# 07_ux.net
KiCad netlist of a schematic drawn in Altium Designer
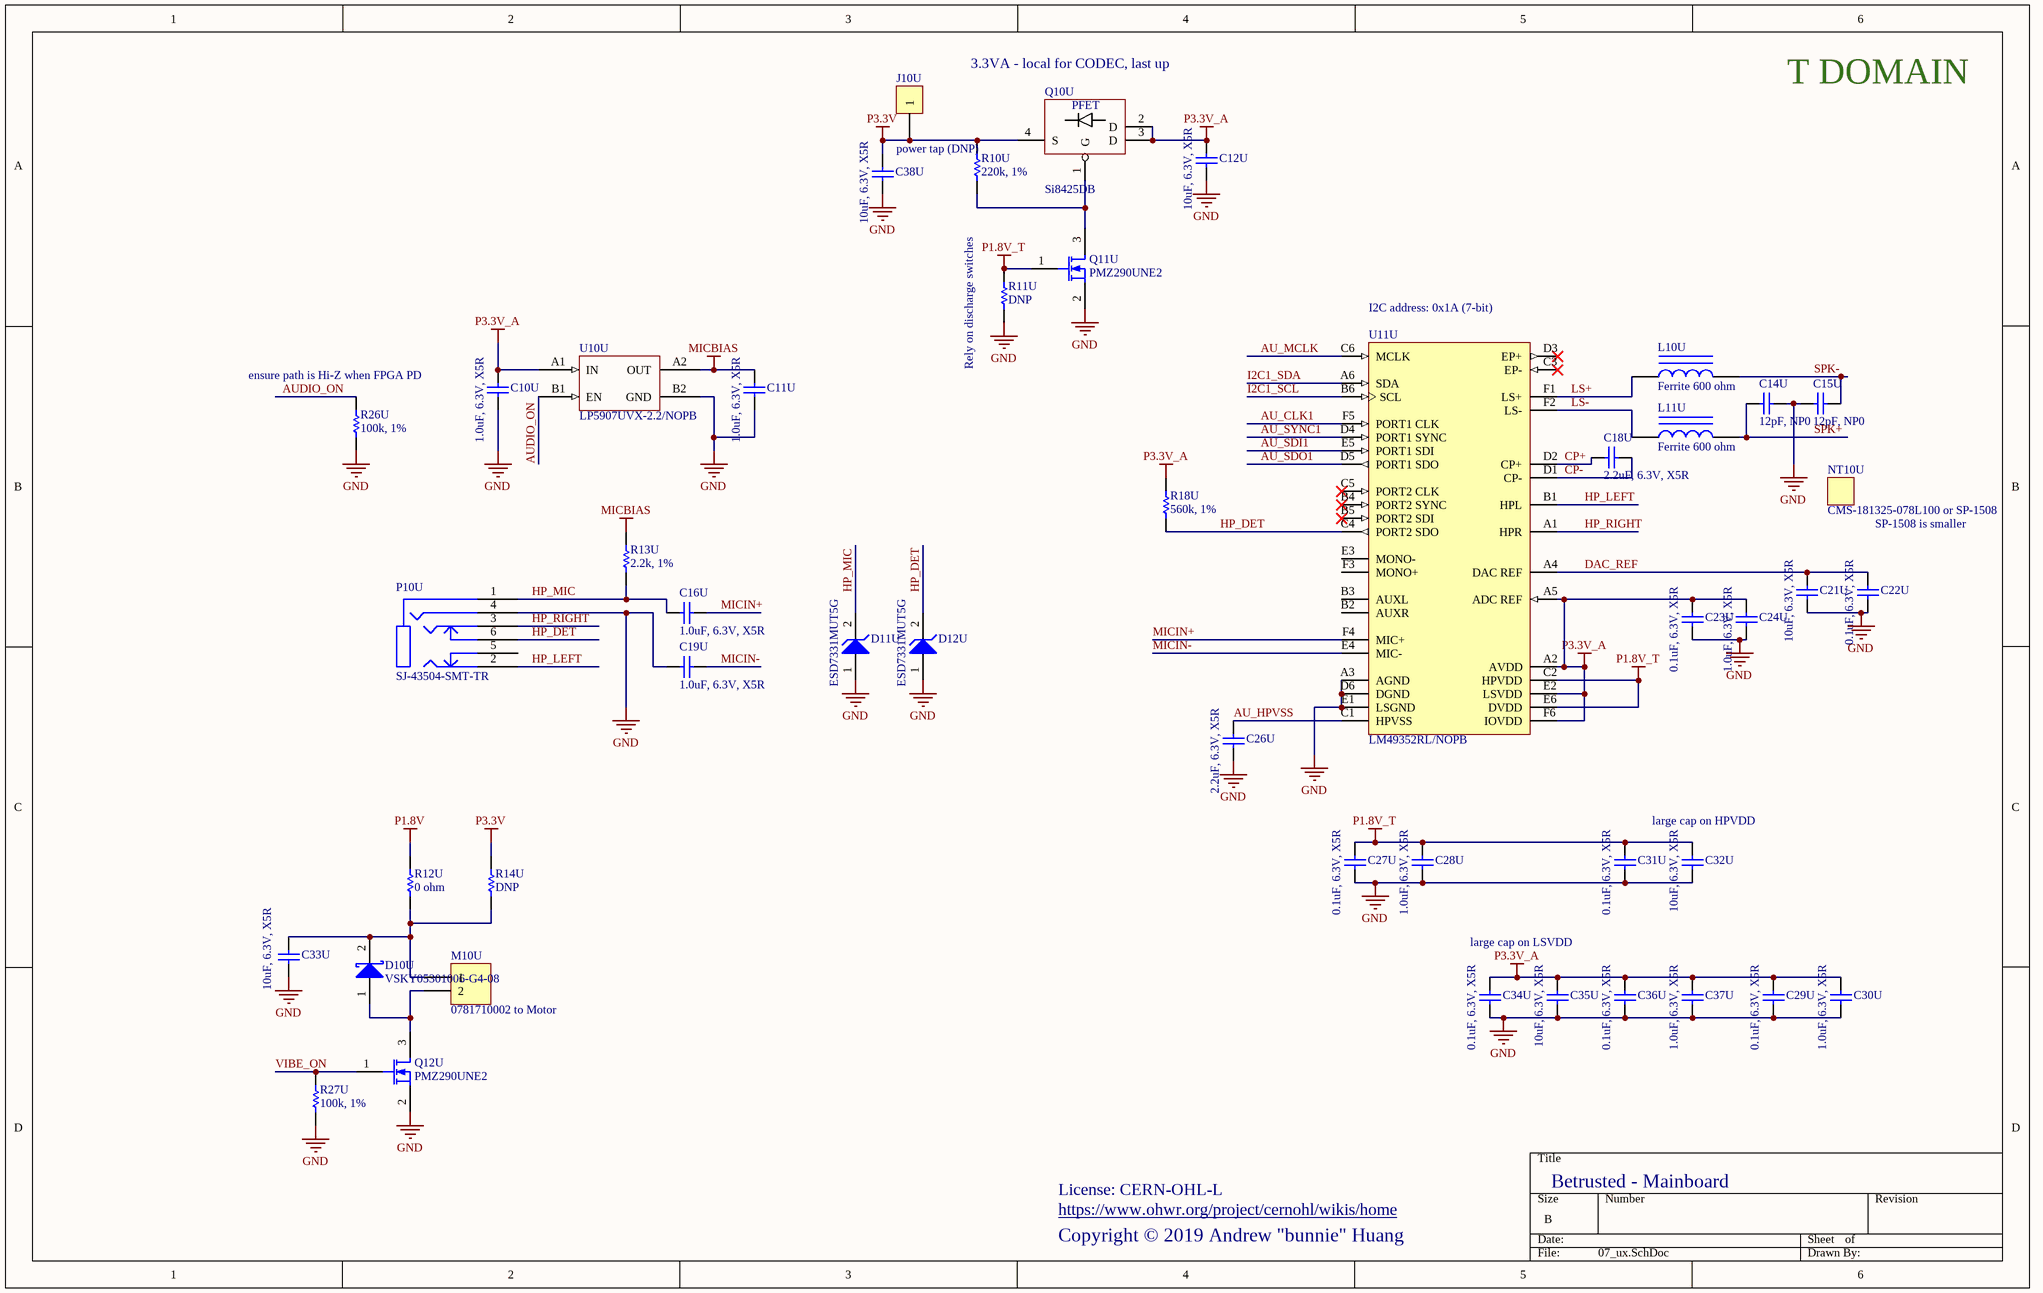
[diagram p0: 07_ux.SchDoc]

(export (version "E")
  (design (tool "Eeschema 10.0.6"))
  (components
    (comp (ref "C10U")
      (value "1.0uF, 6.3V, X5R")
      (footprint "B_CAP0201")
      (description "Capacitor (Semiconductor SIM Model)")
      (fields (field (name "MPN") "GRM033R60J105MEA2D"))
      (libsource (lib "Miscellaneous Devices") (part "Cap Semi"))
    )
    (comp (ref "C11U")
      (value "1.0uF, 6.3V, X5R")
      (footprint "B_CAP0201")
      (description "Capacitor (Semiconductor SIM Model)")
      (fields (field (name "MPN") "GRM033R60J105MEA2D"))
      (libsource (lib "Miscellaneous Devices") (part "Cap Semi"))
    )
    (comp (ref "C12U")
      (value "10uF, 6.3V, X5R")
      (footprint "B_CAP0603")
      (description "Capacitor (Semiconductor SIM Model)")
      (fields (field (name "MPN") "CL10A106MQ8NNNC"))
      (libsource (lib "Miscellaneous Devices") (part "Cap Semi"))
    )
    (comp (ref "C14U")
      (value "12pF, NP0")
      (footprint "B_CAP0201")
      (description "Capacitor (Semiconductor SIM Model)")
      (fields (field (name "MPN") "GRM0335C1E120JA01D"))
      (libsource (lib "Miscellaneous Devices") (part "Cap Semi"))
    )
    (comp (ref "C15U")
      (value "12pF, NP0")
      (footprint "B_CAP0201")
      (description "Capacitor (Semiconductor SIM Model)")
      (fields (field (name "MPN") "GRM0335C1E120JA01D"))
      (libsource (lib "Miscellaneous Devices") (part "Cap Semi"))
    )
    (comp (ref "C16U")
      (value "1.0uF, 6.3V, X5R")
      (footprint "B_CAP0201")
      (description "Capacitor (Semiconductor SIM Model)")
      (fields (field (name "MPN") "GRM033R60J105MEA2D"))
      (libsource (lib "Miscellaneous Devices") (part "Cap Semi"))
    )
    (comp (ref "C18U")
      (value "2.2uF, 6.3V, X5R")
      (footprint "B_CAP0402")
      (description "Capacitor (Semiconductor SIM Model)")
      (fields (field (name "MPN") "CL05A225MQ5NNNC"))
      (libsource (lib "Miscellaneous Devices") (part "Cap Semi"))
    )
    (comp (ref "C19U")
      (value "1.0uF, 6.3V, X5R")
      (footprint "B_CAP0201")
      (description "Capacitor (Semiconductor SIM Model)")
      (fields (field (name "MPN") "GRM033R60J105MEA2D"))
      (libsource (lib "Miscellaneous Devices") (part "Cap Semi"))
    )
    (comp (ref "C21U")
      (value "10uF, 6.3V, X5R")
      (footprint "B_CAP0603")
      (description "Capacitor (Semiconductor SIM Model)")
      (fields (field (name "MPN") "CL10A106MQ8NNNC"))
      (libsource (lib "Miscellaneous Devices") (part "Cap Semi"))
    )
    (comp (ref "C22U")
      (value "0.1uF, 6.3V, X5R")
      (footprint "B_CAP0201")
      (description "Capacitor (Semiconductor SIM Model)")
      (fields (field (name "MPN") "CL03A104KQ3NNNC"))
      (libsource (lib "Miscellaneous Devices") (part "Cap Semi"))
    )
    (comp (ref "C23U")
      (value "0.1uF, 6.3V, X5R")
      (footprint "B_CAP0201")
      (description "Capacitor (Semiconductor SIM Model)")
      (fields (field (name "MPN") "CL03A104KQ3NNNC"))
      (libsource (lib "Miscellaneous Devices") (part "Cap Semi"))
    )
    (comp (ref "C24U")
      (value "1.0uF, 6.3V, X5R")
      (footprint "B_CAP0201")
      (description "Capacitor (Semiconductor SIM Model)")
      (fields (field (name "MPN") "GRM033R60J105MEA2D"))
      (libsource (lib "Miscellaneous Devices") (part "Cap Semi"))
    )
    (comp (ref "C26U")
      (value "2.2uF, 6.3V, X5R")
      (footprint "B_CAP0402")
      (description "Capacitor (Semiconductor SIM Model)")
      (fields (field (name "MPN") "CL05A225MQ5NNNC"))
      (libsource (lib "Miscellaneous Devices") (part "Cap Semi"))
    )
    (comp (ref "C27U")
      (value "0.1uF, 6.3V, X5R")
      (footprint "B_CAP0201")
      (description "Capacitor (Semiconductor SIM Model)")
      (fields (field (name "MPN") "CL03A104KQ3NNNC"))
      (libsource (lib "Miscellaneous Devices") (part "Cap Semi"))
    )
    (comp (ref "C28U")
      (value "1.0uF, 6.3V, X5R")
      (footprint "B_CAP0201")
      (description "Capacitor (Semiconductor SIM Model)")
      (fields (field (name "MPN") "GRM033R60J105MEA2D"))
      (libsource (lib "Miscellaneous Devices") (part "Cap Semi"))
    )
    (comp (ref "C29U")
      (value "0.1uF, 6.3V, X5R")
      (footprint "B_CAP0201")
      (description "Capacitor (Semiconductor SIM Model)")
      (fields (field (name "MPN") "CL03A104KQ3NNNC"))
      (libsource (lib "Miscellaneous Devices") (part "Cap Semi"))
    )
    (comp (ref "C30U")
      (value "1.0uF, 6.3V, X5R")
      (footprint "B_CAP0201")
      (description "Capacitor (Semiconductor SIM Model)")
      (fields (field (name "MPN") "GRM033R60J105MEA2D"))
      (libsource (lib "Miscellaneous Devices") (part "Cap Semi"))
    )
    (comp (ref "C31U")
      (value "0.1uF, 6.3V, X5R")
      (footprint "B_CAP0201")
      (description "Capacitor (Semiconductor SIM Model)")
      (fields (field (name "MPN") "CL03A104KQ3NNNC"))
      (libsource (lib "Miscellaneous Devices") (part "Cap Semi"))
    )
    (comp (ref "C32U")
      (value "10uF, 6.3V, X5R")
      (footprint "B_CAP0603")
      (description "Capacitor (Semiconductor SIM Model)")
      (fields (field (name "MPN") "CL10A106MQ8NNNC"))
      (libsource (lib "Miscellaneous Devices") (part "Cap Semi"))
    )
    (comp (ref "C33U")
      (value "10uF, 6.3V, X5R")
      (footprint "B_CAP0603")
      (description "Capacitor (Semiconductor SIM Model)")
      (fields (field (name "MPN") "CL10A106MQ8NNNC"))
      (libsource (lib "Miscellaneous Devices") (part "Cap Semi"))
    )
    (comp (ref "C34U")
      (value "0.1uF, 6.3V, X5R")
      (footprint "B_CAP0201")
      (description "Capacitor (Semiconductor SIM Model)")
      (fields (field (name "MPN") "CL03A104KQ3NNNC"))
      (libsource (lib "Miscellaneous Devices") (part "Cap Semi"))
    )
    (comp (ref "C35U")
      (value "10uF, 6.3V, X5R")
      (footprint "B_CAP0603")
      (description "Capacitor (Semiconductor SIM Model)")
      (fields (field (name "MPN") "CL10A106MQ8NNNC"))
      (libsource (lib "Miscellaneous Devices") (part "Cap Semi"))
    )
    (comp (ref "C36U")
      (value "0.1uF, 6.3V, X5R")
      (footprint "B_CAP0201")
      (description "Capacitor (Semiconductor SIM Model)")
      (fields (field (name "MPN") "CL03A104KQ3NNNC"))
      (libsource (lib "Miscellaneous Devices") (part "Cap Semi"))
    )
    (comp (ref "C37U")
      (value "1.0uF, 6.3V, X5R")
      (footprint "B_CAP0201")
      (description "Capacitor (Semiconductor SIM Model)")
      (fields (field (name "MPN") "GRM033R60J105MEA2D"))
      (libsource (lib "Miscellaneous Devices") (part "Cap Semi"))
    )
    (comp (ref "C38U")
      (value "10uF, 6.3V, X5R")
      (footprint "B_CAP0603")
      (description "Capacitor (Semiconductor SIM Model)")
      (fields (field (name "MPN") "CL10A106MQ8NNNC"))
      (libsource (lib "Miscellaneous Devices") (part "Cap Semi"))
    )
    (comp (ref "D10U")
      (value "VSKY05301006-G4-08")
      (footprint "B_DIO0402")
      (description "Schottky Rectifier")
      (libsource (lib "Miscellaneous Devices") (part "Diode 11DQ03"))
    )
    (comp (ref "D11U")
      (value "ESD7331MUT5G")
      (footprint "D_X3DFN2_0201")
      (fields (field (name "PUBLISHER") "Altium Limited"))
      (libsource (lib "Miscellaneous Devices") (part "D Zener"))
    )
    (comp (ref "D12U")
      (value "ESD7331MUT5G")
      (footprint "D_X3DFN2_0201")
      (fields (field (name "PUBLISHER") "Altium Limited"))
      (libsource (lib "Miscellaneous Devices") (part "D Zener"))
    )
    (comp (ref "J10U")
      (value "power tap (DNP)")
      (footprint "RESTAP-0603")
      (description "Connector")
      (fields (field (name "MPN") "DNP"))
      (libsource (lib "*") (part "CON1"))
    )
    (comp (ref "L10U")
      (value "Ferrite 600 ohm")
      (footprint "B_IND0603")
      (description "Magnetic-Core Inductor")
      (fields (field (name "MPN") "BLM18AG601SN1D"))
      (libsource (lib "Miscellaneous Devices") (part "Inductor Iron"))
    )
    (comp (ref "L11U")
      (value "Ferrite 600 ohm")
      (footprint "B_IND0603")
      (description "Magnetic-Core Inductor")
      (fields (field (name "MPN") "BLM18AG601SN1D"))
      (libsource (lib "Miscellaneous Devices") (part "Inductor Iron"))
    )
    (comp (ref "M10U")
      (value "0781710002 to Motor")
      (footprint "MOLEX_0781710002")
      (description "Vibration motor, mid-mount 10mm")
      (fields (field (name "MPN") "0781710002") (field (name "PUBLISHER") "Altium Limited"))
      (libsource (lib "Miscellaneous Connectors") (part "Header 2"))
    )
    (comp (ref "NT10U")
      (value "CMS-181325-078L100 or SP-1508")
      (description "Placeholder for non-board BOM items")
      (libsource (lib "commonsch") (part "NOTE"))
    )
    (comp (ref "P10U")
      (value "SJ-43504-SMT-TR")
      (footprint "CUI_SJ_43504_SMT_TR_FLIP")
      (description "Mid mount audio jack")
      (libsource (lib "commonsch-new") (part "CUI_3.5MM_STEREO_MIC"))
    )
    (comp (ref "Q10U")
      (value "Si8425DB")
      (footprint "VISHAY_MICRO_FOOT_4_BUMP")
      (description "P-channel 20V 6.2A 27mOhm @ -2.5V")
      (fields (field (name "MPN") "SI8457DB-T1-E1"))
      (libsource (lib "temp-to-merge") (part "Si8425DB"))
    )
    (comp (ref "Q11U")
      (value "PMZ290UNE2")
      (footprint "SOT883")
      (description "N-Channel MOSFET")
      (fields (field (name "PUBLISHER") "Altium Limited"))
      (libsource (lib "Miscellaneous Devices") (part "MOSFET-N"))
    )
    (comp (ref "Q12U")
      (value "PMZ290UNE2")
      (footprint "SOT883")
      (description "N-Channel MOSFET")
      (fields (field (name "PUBLISHER") "Altium Limited"))
      (libsource (lib "Miscellaneous Devices") (part "MOSFET-N"))
    )
    (comp (ref "R10U")
      (value "220k, 1%")
      (footprint "B_RES0201")
      (description "Resistor")
      (fields (field (name "MPN") "ANY"))
      (libsource (lib "Miscellaneous Devices") (part "Res1"))
    )
    (comp (ref "R11U")
      (value "DNP")
      (footprint "B_RES0201")
      (description "Resistor")
      (fields (field (name "MPN") "ANY"))
      (libsource (lib "Miscellaneous Devices") (part "Res1"))
    )
    (comp (ref "R12U")
      (value "0 ohm")
      (footprint "B_RES0201")
      (description "Resistor")
      (fields (field (name "MPN") "ANY"))
      (libsource (lib "Miscellaneous Devices") (part "Res1"))
    )
    (comp (ref "R13U")
      (value "2.2k, 1%")
      (footprint "B_RES0201")
      (description "Resistor")
      (fields (field (name "MPN") "ANY"))
      (libsource (lib "Miscellaneous Devices") (part "Res1"))
    )
    (comp (ref "R14U")
      (value "DNP")
      (footprint "B_RES0201")
      (description "Resistor")
      (fields (field (name "MPN") "ANY"))
      (libsource (lib "Miscellaneous Devices") (part "Res1"))
    )
    (comp (ref "R18U")
      (value "560k, 1%")
      (footprint "B_RES0201")
      (description "Resistor")
      (fields (field (name "MPN") "ANY"))
      (libsource (lib "Miscellaneous Devices") (part "Res1"))
    )
    (comp (ref "R26U")
      (value "100k, 1%")
      (footprint "B_RES0201")
      (description "Resistor")
      (fields (field (name "MPN") "ANY"))
      (libsource (lib "Miscellaneous Devices") (part "Res1"))
    )
    (comp (ref "R27U")
      (value "100k, 1%")
      (footprint "B_RES0201")
      (description "Resistor")
      (fields (field (name "MPN") "ANY"))
      (libsource (lib "Miscellaneous Devices") (part "Res1"))
    )
    (comp (ref "U10U")
      (value "LP5907UVX-2.2/NOPB")
      (footprint "TI_YKE004")
      (description "Ultra low-noise 250mA LDO for RF and analog in DSBGA")
      (libsource (lib "commonsch-new") (part "LP5907UVX"))
    )
    (comp (ref "U11U")
      (value "LM49352RL/NOPB")
      (footprint "YPG0036AWAW")
      (libsource (lib "Copy of AMP-AUDA-LM49352-36-bunnie") (part "AMP-AUDA-LM49352-36"))
    )
  )
  (nets
    (net (code "1") (name "/AUDIO_ON") (class "Default")
      (node (ref "R26U") (pin "2") (pinfunction "2_2") (pintype "passive"))
      (node (ref "U10U") (pin "B1") (pinfunction "EN_B1") (pintype "input"))
    )
    (net (code "2") (name "/AU_CLK1") (class "Default")
      (node (ref "U11U") (pin "F5") (pinfunction "PORT1_CLK_F5") (pintype "input"))
    )
    (net (code "3") (name "/AU_HPVSS") (class "Default")
      (node (ref "C26U") (pin "2") (pinfunction "2_2") (pintype "passive"))
      (node (ref "U11U") (pin "C1") (pinfunction "HPVSS_C1") (pintype "power_in"))
    )
    (net (code "4") (name "/AU_MCLK") (class "Default")
      (node (ref "U11U") (pin "C6") (pinfunction "MCLK_C6") (pintype "input"))
    )
    (net (code "5") (name "/AU_SDI1") (class "Default")
      (node (ref "U11U") (pin "E5") (pinfunction "PORT1_SDI_E5") (pintype "input"))
    )
    (net (code "6") (name "/AU_SDO1") (class "Default")
      (node (ref "U11U") (pin "D5") (pinfunction "PORT1_SDO_D5") (pintype "output"))
    )
    (net (code "7") (name "/AU_SYNC1") (class "Default")
      (node (ref "U11U") (pin "D4") (pinfunction "PORT1_SYNC_D4") (pintype "input"))
    )
    (net (code "8") (name "/CP+") (class "Default")
      (node (ref "C18U") (pin "2") (pinfunction "2_2") (pintype "passive"))
      (node (ref "U11U") (pin "D2") (pinfunction "CP+_D2") (pintype "passive"))
    )
    (net (code "9") (name "/CP-") (class "Default")
      (node (ref "C18U") (pin "1") (pinfunction "1_1") (pintype "passive"))
      (node (ref "U11U") (pin "D1") (pinfunction "CP-_D1") (pintype "passive"))
    )
    (net (code "10") (name "/DAC_REF") (class "Default")
      (node (ref "C21U") (pin "1") (pinfunction "1_1") (pintype "passive"))
      (node (ref "C22U") (pin "1") (pinfunction "1_1") (pintype "passive"))
      (node (ref "U11U") (pin "A4") (pinfunction "DAC_REF_A4") (pintype "power_in"))
    )
    (net (code "11") (name "/HP_DET") (class "Default")
      (node (ref "D12U") (pin "2") (pinfunction "K_2") (pintype "passive"))
      (node (ref "P10U") (pin "6") (pinfunction "RING1_SW_6") (pintype "passive"))
      (node (ref "R18U") (pin "1") (pinfunction "1_1") (pintype "passive"))
      (node (ref "U11U") (pin "C4") (pinfunction "PORT2_SDO_C4") (pintype "output"))
    )
    (net (code "12") (name "/HP_LEFT") (class "Default")
      (node (ref "P10U") (pin "2") (pinfunction "TIP_2") (pintype "passive"))
      (node (ref "U11U") (pin "B1") (pinfunction "HPL_B1") (pintype "passive"))
    )
    (net (code "13") (name "/HP_MIC") (class "Default")
      (node (ref "C16U") (pin "1") (pinfunction "1_1") (pintype "passive"))
      (node (ref "D11U") (pin "2") (pinfunction "K_2") (pintype "passive"))
      (node (ref "P10U") (pin "1") (pinfunction "SLEEVE_1") (pintype "passive"))
      (node (ref "R13U") (pin "1") (pinfunction "1_1") (pintype "passive"))
    )
    (net (code "14") (name "/HP_RIGHT") (class "Default")
      (node (ref "P10U") (pin "3") (pinfunction "RING1_3") (pintype "passive"))
      (node (ref "U11U") (pin "A1") (pinfunction "HPR_A1") (pintype "passive"))
    )
    (net (code "15") (name "/I2C1_SCL") (class "Default")
      (node (ref "U11U") (pin "B6") (pinfunction "SCL_B6") (pintype "input"))
    )
    (net (code "16") (name "/I2C1_SDA") (class "Default")
      (node (ref "U11U") (pin "A6") (pinfunction "SDA_A6") (pintype "input"))
    )
    (net (code "17") (name "/LS+") (class "Default")
      (node (ref "L10U") (pin "1") (pinfunction "1_1") (pintype "passive"))
      (node (ref "U11U") (pin "F1") (pinfunction "LS+_F1") (pintype "power_in"))
    )
    (net (code "18") (name "/LS-") (class "Default")
      (node (ref "L11U") (pin "1") (pinfunction "1_1") (pintype "passive"))
      (node (ref "U11U") (pin "F2") (pinfunction "LS-_F2") (pintype "power_in"))
    )
    (net (code "19") (name "/MICIN+") (class "Default")
      (node (ref "C16U") (pin "2") (pinfunction "2_2") (pintype "passive"))
      (node (ref "U11U") (pin "F4") (pinfunction "MIC+_F4") (pintype "passive"))
    )
    (net (code "20") (name "/MICIN-") (class "Default")
      (node (ref "C19U") (pin "2") (pinfunction "2_2") (pintype "passive"))
      (node (ref "U11U") (pin "E4") (pinfunction "MIC-_E4") (pintype "passive"))
    )
    (net (code "21") (name "/SPK+") (class "Default")
      (node (ref "C14U") (pin "1") (pinfunction "1_1") (pintype "passive"))
      (node (ref "L11U") (pin "2") (pinfunction "2_2") (pintype "passive"))
    )
    (net (code "22") (name "/SPK-") (class "Default")
      (node (ref "C15U") (pin "2") (pinfunction "2_2") (pintype "passive"))
      (node (ref "L10U") (pin "2") (pinfunction "2_2") (pintype "passive"))
    )
    (net (code "23") (name "/VIBE_ON") (class "Default")
      (node (ref "Q12U") (pin "1") (pinfunction "G_1") (pintype "passive"))
      (node (ref "R27U") (pin "2") (pinfunction "2_2") (pintype "passive"))
    )
    (net (code "24") (name "GND") (class "Default")
      (node (ref "C10U") (pin "2") (pinfunction "2_2") (pintype "passive"))
      (node (ref "C11U") (pin "2") (pinfunction "2_2") (pintype "passive"))
      (node (ref "C12U") (pin "2") (pinfunction "2_2") (pintype "passive"))
      (node (ref "C14U") (pin "2") (pinfunction "2_2") (pintype "passive"))
      (node (ref "C15U") (pin "1") (pinfunction "1_1") (pintype "passive"))
      (node (ref "C19U") (pin "1") (pinfunction "1_1") (pintype "passive"))
      (node (ref "C21U") (pin "2") (pinfunction "2_2") (pintype "passive"))
      (node (ref "C22U") (pin "2") (pinfunction "2_2") (pintype "passive"))
      (node (ref "C23U") (pin "2") (pinfunction "2_2") (pintype "passive"))
      (node (ref "C24U") (pin "1") (pinfunction "1_1") (pintype "passive"))
      (node (ref "C26U") (pin "1") (pinfunction "1_1") (pintype "passive"))
      (node (ref "C27U") (pin "2") (pinfunction "2_2") (pintype "passive"))
      (node (ref "C28U") (pin "1") (pinfunction "1_1") (pintype "passive"))
      (node (ref "C29U") (pin "2") (pinfunction "2_2") (pintype "passive"))
      (node (ref "C30U") (pin "1") (pinfunction "1_1") (pintype "passive"))
      (node (ref "C31U") (pin "2") (pinfunction "2_2") (pintype "passive"))
      (node (ref "C32U") (pin "2") (pinfunction "2_2") (pintype "passive"))
      (node (ref "C33U") (pin "1") (pinfunction "1_1") (pintype "passive"))
      (node (ref "C34U") (pin "2") (pinfunction "2_2") (pintype "passive"))
      (node (ref "C35U") (pin "2") (pinfunction "2_2") (pintype "passive"))
      (node (ref "C36U") (pin "2") (pinfunction "2_2") (pintype "passive"))
      (node (ref "C37U") (pin "1") (pinfunction "1_1") (pintype "passive"))
      (node (ref "C38U") (pin "2") (pinfunction "2_2") (pintype "passive"))
      (node (ref "D11U") (pin "1") (pinfunction "A_1") (pintype "passive"))
      (node (ref "D12U") (pin "1") (pinfunction "A_1") (pintype "passive"))
      (node (ref "P10U") (pin "4") (pinfunction "RING2_4") (pintype "passive"))
      (node (ref "Q11U") (pin "2") (pinfunction "S_2") (pintype "passive"))
      (node (ref "Q12U") (pin "2") (pinfunction "S_2") (pintype "passive"))
      (node (ref "R11U") (pin "1") (pinfunction "1_1") (pintype "passive"))
      (node (ref "R26U") (pin "1") (pinfunction "1_1") (pintype "passive"))
      (node (ref "R27U") (pin "1") (pinfunction "1_1") (pintype "passive"))
      (node (ref "U10U") (pin "B2") (pinfunction "GND_B2") (pintype "power_in"))
      (node (ref "U11U") (pin "A3") (pinfunction "AGND_A3") (pintype "power_in"))
      (node (ref "U11U") (pin "D6") (pinfunction "DGND_D6") (pintype "power_in"))
      (node (ref "U11U") (pin "E1") (pinfunction "LSGND_E1") (pintype "power_in"))
    )
    (net (code "25") (name "MICBIAS") (class "Default")
      (node (ref "C11U") (pin "1") (pinfunction "1_1") (pintype "passive"))
      (node (ref "R13U") (pin "2") (pinfunction "2_2") (pintype "passive"))
      (node (ref "U10U") (pin "A2") (pinfunction "OUT_A2") (pintype "power_in"))
    )
    (net (code "26") (name "Net-(D10U-A)") (class "Default")
      (node (ref "D10U") (pin "1") (pinfunction "A_1") (pintype "passive"))
      (node (ref "M10U") (pin "2") (pinfunction "2_2") (pintype "passive"))
      (node (ref "Q12U") (pin "3") (pinfunction "D_3") (pintype "passive"))
    )
    (net (code "27") (name "Net-(D10U-K)") (class "Default")
      (node (ref "C33U") (pin "2") (pinfunction "2_2") (pintype "passive"))
      (node (ref "D10U") (pin "2") (pinfunction "K_2") (pintype "passive"))
      (node (ref "M10U") (pin "1") (pinfunction "1_1") (pintype "passive"))
      (node (ref "R12U") (pin "1") (pinfunction "1_1") (pintype "passive"))
      (node (ref "R14U") (pin "2") (pinfunction "2_2") (pintype "passive"))
    )
    (net (code "28") (name "Net-(Q10U-G)") (class "Default")
      (node (ref "Q10U") (pin "1") (pinfunction "G_1") (pintype "passive"))
      (node (ref "Q11U") (pin "3") (pinfunction "D_3") (pintype "passive"))
      (node (ref "R10U") (pin "1") (pinfunction "1_1") (pintype "passive"))
    )
    (net (code "29") (name "P1.8V") (class "Default")
      (node (ref "R12U") (pin "2") (pinfunction "2_2") (pintype "passive"))
    )
    (net (code "30") (name "P1.8V_T") (class "Default")
      (node (ref "C27U") (pin "1") (pinfunction "1_1") (pintype "passive"))
      (node (ref "C28U") (pin "2") (pinfunction "2_2") (pintype "passive"))
      (node (ref "C31U") (pin "1") (pinfunction "1_1") (pintype "passive"))
      (node (ref "C32U") (pin "1") (pinfunction "1_1") (pintype "passive"))
      (node (ref "Q11U") (pin "1") (pinfunction "G_1") (pintype "passive"))
      (node (ref "R11U") (pin "2") (pinfunction "2_2") (pintype "passive"))
      (node (ref "U11U") (pin "C2") (pinfunction "HPVDD_C2") (pintype "power_in"))
      (node (ref "U11U") (pin "E6") (pinfunction "DVDD_E6") (pintype "power_in"))
    )
    (net (code "31") (name "P3.3V") (class "Default")
      (node (ref "C38U") (pin "1") (pinfunction "1_1") (pintype "passive"))
      (node (ref "J10U") (pin "1") (pinfunction "1_1") (pintype "passive"))
      (node (ref "Q10U") (pin "4") (pinfunction "S_4") (pintype "passive"))
      (node (ref "R10U") (pin "2") (pinfunction "2_2") (pintype "passive"))
      (node (ref "R14U") (pin "1") (pinfunction "1_1") (pintype "passive"))
    )
    (net (code "32") (name "P3.3V_A") (class "Default")
      (node (ref "C10U") (pin "1") (pinfunction "1_1") (pintype "passive"))
      (node (ref "C12U") (pin "1") (pinfunction "1_1") (pintype "passive"))
      (node (ref "C23U") (pin "1") (pinfunction "1_1") (pintype "passive"))
      (node (ref "C24U") (pin "2") (pinfunction "2_2") (pintype "passive"))
      (node (ref "C29U") (pin "1") (pinfunction "1_1") (pintype "passive"))
      (node (ref "C30U") (pin "2") (pinfunction "2_2") (pintype "passive"))
      (node (ref "C34U") (pin "1") (pinfunction "1_1") (pintype "passive"))
      (node (ref "C35U") (pin "1") (pinfunction "1_1") (pintype "passive"))
      (node (ref "C36U") (pin "1") (pinfunction "1_1") (pintype "passive"))
      (node (ref "C37U") (pin "2") (pinfunction "2_2") (pintype "passive"))
      (node (ref "Q10U") (pin "2") (pinfunction "D_2") (pintype "passive"))
      (node (ref "Q10U") (pin "3") (pinfunction "D_3") (pintype "passive"))
      (node (ref "R18U") (pin "2") (pinfunction "2_2") (pintype "passive"))
      (node (ref "U10U") (pin "A1") (pinfunction "IN_A1") (pintype "input"))
      (node (ref "U11U") (pin "A2") (pinfunction "AVDD_A2") (pintype "power_in"))
      (node (ref "U11U") (pin "A5") (pinfunction "ADC_REF_A5") (pintype "input"))
      (node (ref "U11U") (pin "E2") (pinfunction "LSVDD_E2") (pintype "power_in"))
      (node (ref "U11U") (pin "F6") (pinfunction "IOVDD_F6") (pintype "power_in"))
    )
    (net (code "33") (name "unconnected-(P10U-TIP_SW-Pad5)") (class "Default")
      (node (ref "P10U") (pin "5") (pinfunction "TIP_SW_5") (pintype "passive"))
    )
    (net (code "34") (name "unconnected-(U11U-AUXL-PadB3)") (class "Default")
      (node (ref "U11U") (pin "B3") (pinfunction "AUXL_B3") (pintype "passive"))
    )
    (net (code "35") (name "unconnected-(U11U-AUXR-PadB2)") (class "Default")
      (node (ref "U11U") (pin "B2") (pinfunction "AUXR_B2") (pintype "passive"))
    )
    (net (code "36") (name "unconnected-(U11U-EP+-PadD3)") (class "Default")
      (node (ref "U11U") (pin "D3") (pinfunction "EP+_D3") (pintype "output+no_connect"))
    )
    (net (code "37") (name "unconnected-(U11U-EP--PadC3)") (class "Default")
      (node (ref "U11U") (pin "C3") (pinfunction "EP-_C3") (pintype "input+no_connect"))
    )
    (net (code "38") (name "unconnected-(U11U-MONO+-PadF3)") (class "Default")
      (node (ref "U11U") (pin "F3") (pinfunction "MONO+_F3") (pintype "passive"))
    )
    (net (code "39") (name "unconnected-(U11U-MONO--PadE3)") (class "Default")
      (node (ref "U11U") (pin "E3") (pinfunction "MONO-_E3") (pintype "passive"))
    )
    (net (code "40") (name "unconnected-(U11U-PORT2_CLK-PadC5)") (class "Default")
      (node (ref "U11U") (pin "C5") (pinfunction "PORT2_CLK_C5") (pintype "input+no_connect"))
    )
    (net (code "41") (name "unconnected-(U11U-PORT2_SDI-PadB5)") (class "Default")
      (node (ref "U11U") (pin "B5") (pinfunction "PORT2_SDI_B5") (pintype "input+no_connect"))
    )
    (net (code "42") (name "unconnected-(U11U-PORT2_SYNC-PadB4)") (class "Default")
      (node (ref "U11U") (pin "B4") (pinfunction "PORT2_SYNC_B4") (pintype "input+no_connect"))
    )
  )
)
